# HornRelay.net
KiCad netlist of a schematic drawn in Altium Designer
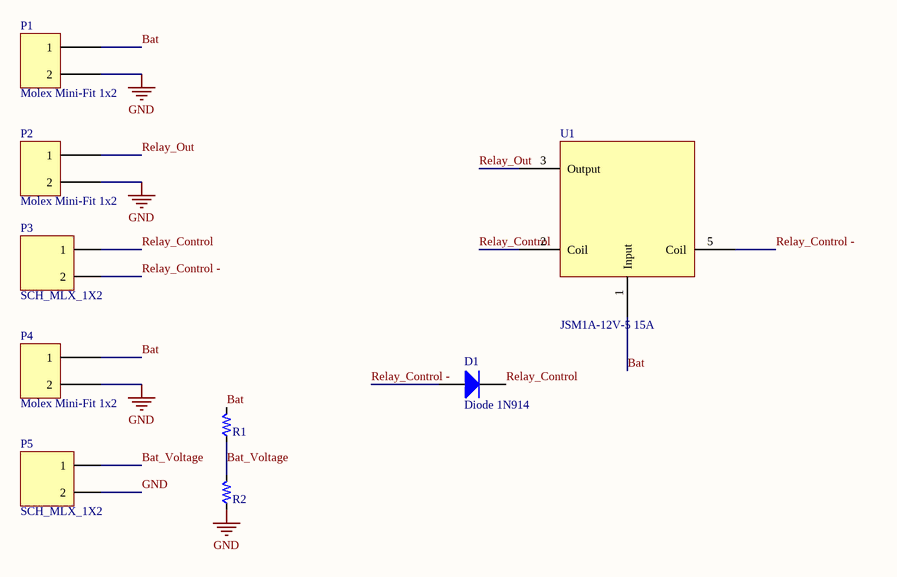
[diagram p0: HornRelay.SchDoc]

(export (version "E")
  (design (tool "Eeschema 10.0.6"))
  (components
    (comp (ref "D1")
      (value "Diode 1N914")
      (footprint "DO-35")
      (description "High Conductance Fast Diode")
      (fields (field (name "PUBLISHER") "Altium Limited"))
      (libsource (lib "Miscellaneous Devices") (part "Diode 1N914"))
    )
    (comp (ref "P1")
      (value "Molex Mini-Fit 1x2")
      (footprint "Molex Mini-Fit Jr 2x1")
      (libsource (lib "Molex Mini-Fit Jr 1x2") (part "Molex Mini-Fit 1x2"))
    )
    (comp (ref "P2")
      (value "Molex Mini-Fit 1x2")
      (footprint "Molex Mini-Fit Jr 2x1")
      (libsource (lib "Molex Mini-Fit Jr 1x2") (part "Molex Mini-Fit 1x2"))
    )
    (comp (ref "P3")
      (value "SCH_MLX_1X2")
      (footprint "PCB_MLX_MICROFIT_1X2")
      (libsource (lib "Molex Microfit 3.0 1x2") (part "SCH_MLX_1X2"))
    )
    (comp (ref "P4")
      (value "Molex Mini-Fit 1x2")
      (footprint "Molex Mini-Fit Jr 2x1")
      (libsource (lib "Molex Mini-Fit Jr 1x2") (part "Molex Mini-Fit 1x2"))
    )
    (comp (ref "P5")
      (value "SCH_MLX_1X2")
      (footprint "PCB_MLX_MICROFIT_1X2")
      (libsource (lib "Molex Microfit 3.0 1x2") (part "SCH_MLX_1X2"))
    )
    (comp (ref "R1")
      (value "4.7k")
      (footprint "PCB_GENERIC_SMD_0603")
      (description "Generic SMD resistor 0603")
      (libsource (lib "Generic 0603 Resistor") (part "SCH_GENERIC_RESISTOR_0603"))
    )
    (comp (ref "R2")
      (value "1k")
      (footprint "PCB_GENERIC_SMD_0603")
      (description "Generic SMD resistor 0603")
      (libsource (lib "Generic 0603 Resistor") (part "SCH_GENERIC_RESISTOR_0603"))
    )
    (comp (ref "U1")
      (value "JSM1A-12V-5 15A")
      (footprint "JSM1A-12V-5 15A")
      (description "15A Relay 255-2815-ND")
      (libsource (lib "JSM1A-12V-5 15A") (part "JSM1A-12V-5 15A"))
    )
  )
  (nets
    (net (code "1") (name "/Bat") (class "Default")
      (node (ref "P1") (pin "1") (pinfunction "1_1") (pintype "passive"))
      (node (ref "P4") (pin "1") (pinfunction "1_1") (pintype "passive"))
      (node (ref "R1") (pin "2") (pinfunction "2_2") (pintype "passive"))
      (node (ref "U1") (pin "1") (pinfunction "Input_1") (pintype "passive"))
    )
    (net (code "2") (name "/Bat_Voltage") (class "Default")
      (node (ref "P5") (pin "1") (pinfunction "1_1") (pintype "passive"))
      (node (ref "R1") (pin "1") (pinfunction "1_1") (pintype "passive"))
      (node (ref "R2") (pin "2") (pinfunction "2_2") (pintype "passive"))
    )
    (net (code "3") (name "/Relay_Control") (class "Default")
      (node (ref "D1") (pin "2") (pinfunction "K_2") (pintype "passive"))
      (node (ref "P3") (pin "1") (pinfunction "1_1") (pintype "passive"))
      (node (ref "U1") (pin "2") (pinfunction "Coil_2") (pintype "passive"))
    )
    (net (code "4") (name "/Relay_Control -") (class "Default")
      (node (ref "D1") (pin "1") (pinfunction "A_1") (pintype "passive"))
      (node (ref "P3") (pin "2") (pinfunction "2_2") (pintype "passive"))
      (node (ref "U1") (pin "5") (pinfunction "Coil_5") (pintype "passive"))
    )
    (net (code "5") (name "/Relay_Out") (class "Default")
      (node (ref "P2") (pin "1") (pinfunction "1_1") (pintype "passive"))
      (node (ref "U1") (pin "3") (pinfunction "Output_3") (pintype "passive"))
    )
    (net (code "6") (name "GND") (class "Default")
      (node (ref "P1") (pin "2") (pinfunction "2_2") (pintype "passive"))
      (node (ref "P2") (pin "2") (pinfunction "2_2") (pintype "passive"))
      (node (ref "P4") (pin "2") (pinfunction "2_2") (pintype "passive"))
      (node (ref "P5") (pin "2") (pinfunction "2_2") (pintype "passive"))
      (node (ref "R2") (pin "1") (pinfunction "1_1") (pintype "passive"))
    )
  )
)
